# Pi_Wedge.net
KiCad netlist of a schematic drawn in EAGLE
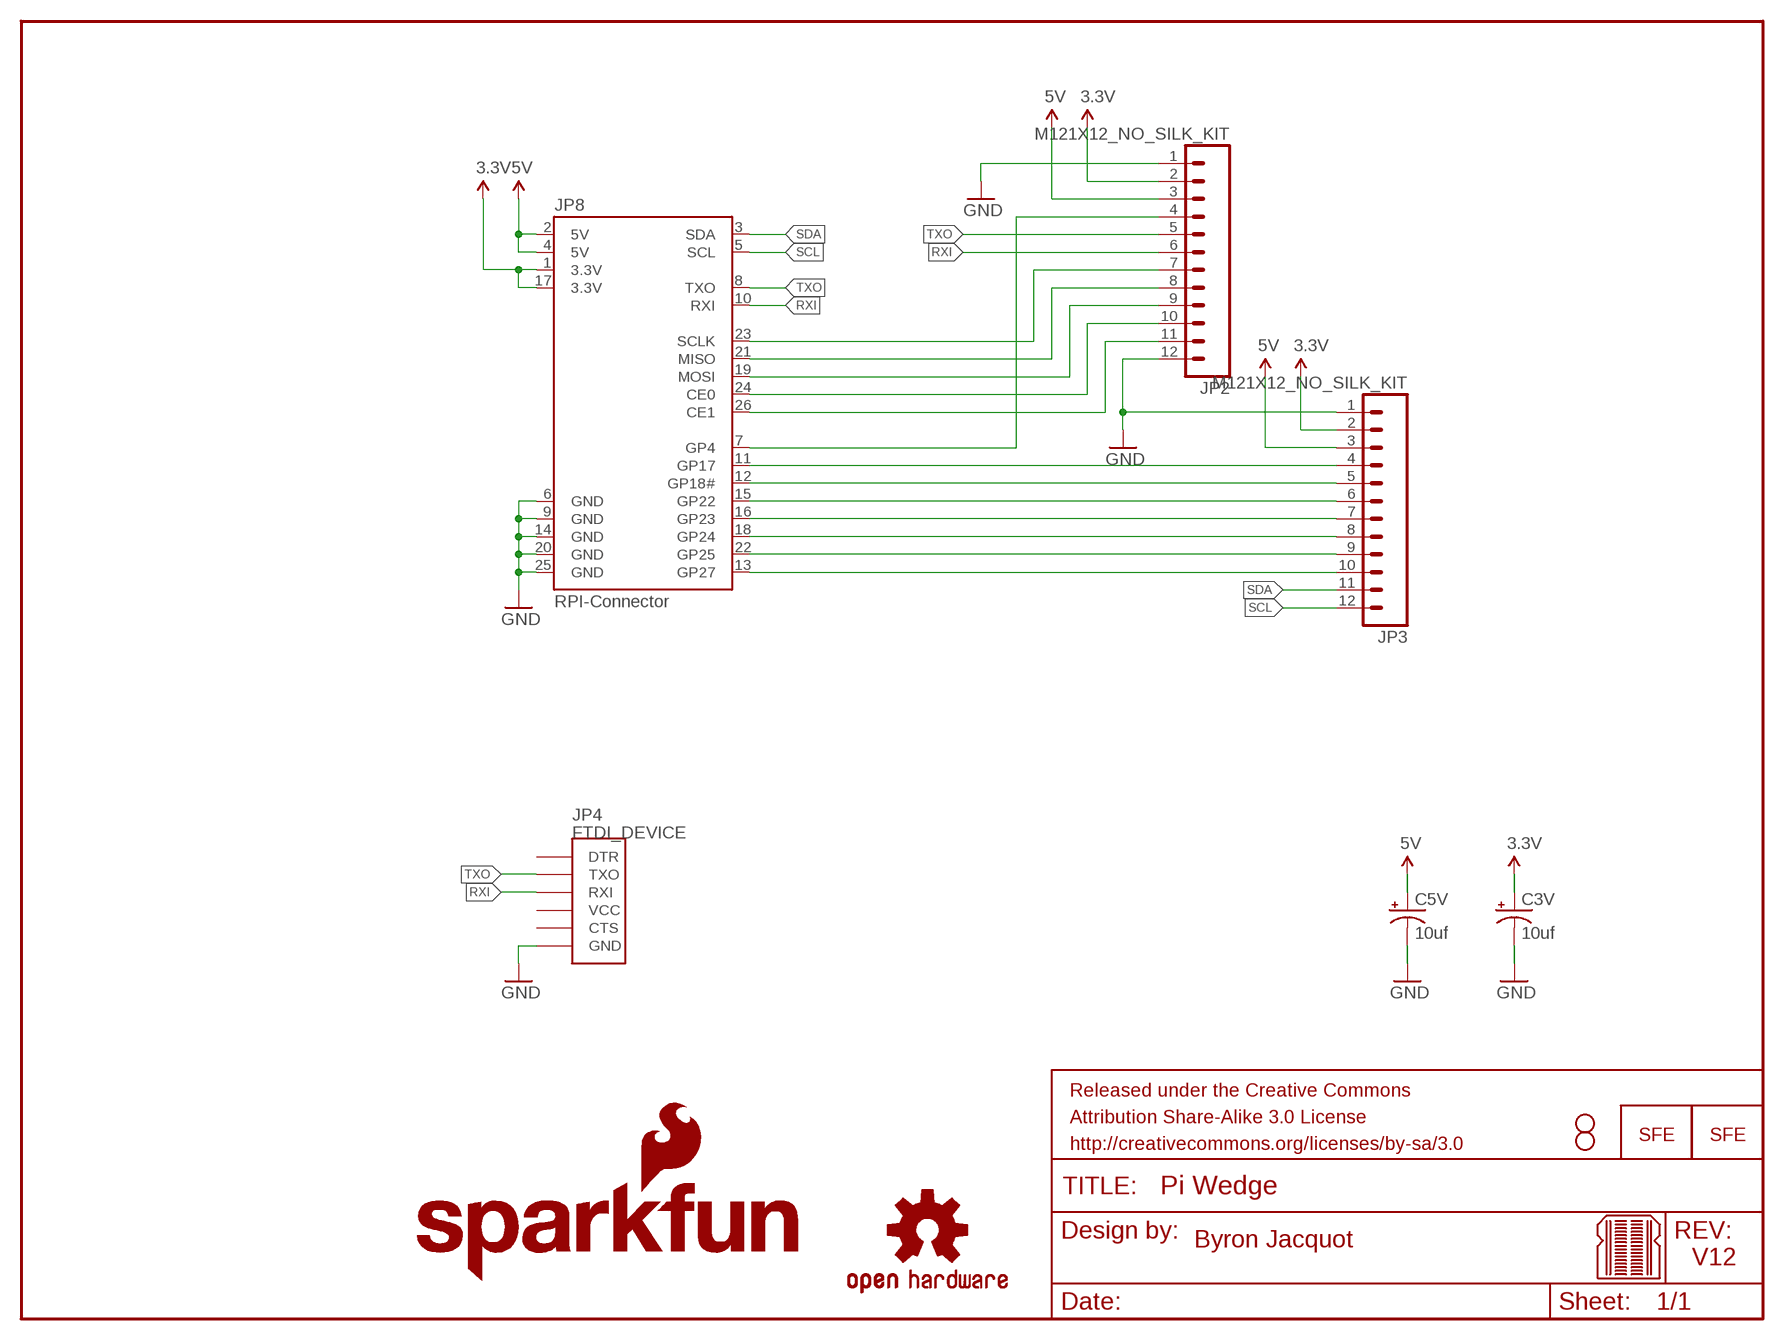
[diagram p0: schematic, sheet 1]

(export (version "E")
  (design (tool "Eeschema 10.0.6"))
  (components
    (comp (ref "C3V")
      (value "10uf")
      (footprint "eagle-import:CPOL-RADIAL-10UF-25V-KIT")
      (libsource (lib "eagle-import") (part "10UF-25V-20%(PTH)KIT"))
    )
    (comp (ref "C5V")
      (value "10uf")
      (footprint "eagle-import:CPOL-RADIAL-10UF-25V-KIT")
      (libsource (lib "eagle-import") (part "10UF-25V-20%(PTH)KIT"))
    )
    (comp (ref "FRAME2")
      (value "FRAME-LETTER")
      (footprint "eagle-import:CREATIVE_COMMONS")
      (libsource (lib "eagle-import") (part "FRAME-LETTER"))
    )
    (comp (ref "JP1")
      (value "LOGO-SFESK")
      (footprint "eagle-import:SFE-LOGO-FLAME")
      (libsource (lib "eagle-import") (part "LOGO-SFESK"))
    )
    (comp (ref "JP2")
      (value "M121X12_NO_SILK_KIT")
      (footprint "eagle-import:1X12_NO_SILK_KIT")
      (libsource (lib "eagle-import") (part "M121X12_NO_SILK_KIT"))
    )
    (comp (ref "JP3")
      (value "M121X12_NO_SILK_KIT")
      (footprint "eagle-import:1X12_NO_SILK_KIT")
      (libsource (lib "eagle-import") (part "M121X12_NO_SILK_KIT"))
    )
    (comp (ref "JP4")
      (value "FTDI_DEVICE")
      (footprint "eagle-import:FTDI_DEVICE_SIDE")
      (libsource (lib "eagle-import") (part "FTDI_DEVICE"))
    )
    (comp (ref "JP5")
      (value "LOGO-SFESK")
      (footprint "eagle-import:SFE-LOGO-FLAME")
      (libsource (lib "eagle-import") (part "LOGO-SFESK"))
    )
    (comp (ref "JP8")
      (value "RPI-Connector")
      (footprint "eagle-import:2X13-SHROUDED")
      (libsource (lib "eagle-import") (part "RASPBERRYPI-GPIOPTH"))
    )
    (comp (ref "LOGO1")
      (value "SFE_LOGO_NAME_FLAME.2_INCH")
      (footprint "eagle-import:SFE_LOGO_NAME_FLAME_.2")
      (libsource (lib "eagle-import") (part "SFE_LOGO_NAME_FLAME.2_INCH"))
    )
    (comp (ref "STANDOFF1")
      (value "STAND-OFF")
      (footprint "eagle-import:STAND-OFF")
      (libsource (lib "eagle-import") (part "STAND-OFF"))
    )
    (comp (ref "STANDOFF2")
      (value "STAND-OFF")
      (footprint "eagle-import:STAND-OFF")
      (libsource (lib "eagle-import") (part "STAND-OFF"))
    )
    (comp (ref "U$1")
      (value "OSHW-LOGOS")
      (footprint "eagle-import:OSHW-LOGO-S")
      (libsource (lib "eagle-import") (part "OSHW-LOGOS"))
    )
    (comp (ref "U$2")
      (value "BREADBOARD_PATTERN")
      (footprint "eagle-import:BREADBOARD_SPACING")
      (libsource (lib "eagle-import") (part "BREADBOARD_PATTERN"))
    )
  )
  (nets
    (net (code "1") (name "3.3V") (class "Default")
      (node (ref "C3V") (pin "1") (pinfunction "+_1") (pintype "passive"))
      (node (ref "JP2") (pin "2") (pinfunction "2_2") (pintype "passive"))
      (node (ref "JP3") (pin "2") (pinfunction "2_2") (pintype "passive"))
      (node (ref "JP8") (pin "1") (pinfunction "3.3V_1") (pintype "power_in"))
      (node (ref "JP8") (pin "17") (pinfunction "3.3V_17") (pintype "power_in"))
    )
    (net (code "2") (name "5V") (class "Default")
      (node (ref "C5V") (pin "1") (pinfunction "+_1") (pintype "passive"))
      (node (ref "JP2") (pin "3") (pinfunction "3_3") (pintype "passive"))
      (node (ref "JP3") (pin "3") (pinfunction "3_3") (pintype "passive"))
      (node (ref "JP8") (pin "2") (pinfunction "5V_2") (pintype "power_in"))
      (node (ref "JP8") (pin "4") (pinfunction "5V_4") (pintype "power_in"))
    )
    (net (code "3") (name "GND") (class "Default")
      (node (ref "C3V") (pin "2") (pinfunction "-_2") (pintype "passive"))
      (node (ref "C5V") (pin "2") (pinfunction "-_2") (pintype "passive"))
      (node (ref "JP2") (pin "1") (pinfunction "1_1") (pintype "passive"))
      (node (ref "JP2") (pin "12") (pinfunction "12_12") (pintype "passive"))
      (node (ref "JP3") (pin "1") (pinfunction "1_1") (pintype "passive"))
      (node (ref "JP4") (pin "P$6") (pinfunction "GND_P$6") (pintype "bidirectional"))
      (node (ref "JP8") (pin "14") (pinfunction "GND_14") (pintype "power_in"))
      (node (ref "JP8") (pin "20") (pinfunction "GND_20") (pintype "power_in"))
      (node (ref "JP8") (pin "25") (pinfunction "GND_25") (pintype "power_in"))
      (node (ref "JP8") (pin "6") (pinfunction "GND_6") (pintype "power_in"))
      (node (ref "JP8") (pin "9") (pinfunction "GND_9") (pintype "power_in"))
    )
    (net (code "4") (name "Net-(JP8-CE0)") (class "Default")
      (node (ref "JP2") (pin "10") (pinfunction "10_10") (pintype "passive"))
      (node (ref "JP8") (pin "24") (pinfunction "CE0_24") (pintype "output"))
    )
    (net (code "5") (name "Net-(JP8-CE1)") (class "Default")
      (node (ref "JP2") (pin "11") (pinfunction "11_11") (pintype "passive"))
      (node (ref "JP8") (pin "26") (pinfunction "CE1_26") (pintype "output"))
    )
    (net (code "6") (name "Net-(JP8-GP4)") (class "Default")
      (node (ref "JP2") (pin "4") (pinfunction "4_4") (pintype "passive"))
      (node (ref "JP8") (pin "7") (pinfunction "GP4_7") (pintype "bidirectional"))
    )
    (net (code "7") (name "Net-(JP8-GP17)") (class "Default")
      (node (ref "JP3") (pin "4") (pinfunction "4_4") (pintype "passive"))
      (node (ref "JP8") (pin "11") (pinfunction "GP17_11") (pintype "bidirectional"))
    )
    (net (code "8") (name "Net-(JP8-GP18#)") (class "Default")
      (node (ref "JP3") (pin "5") (pinfunction "5_5") (pintype "passive"))
      (node (ref "JP8") (pin "12") (pinfunction "GP18#_12") (pintype "bidirectional"))
    )
    (net (code "9") (name "Net-(JP8-GP22)") (class "Default")
      (node (ref "JP3") (pin "6") (pinfunction "6_6") (pintype "passive"))
      (node (ref "JP8") (pin "15") (pinfunction "GP22_15") (pintype "bidirectional"))
    )
    (net (code "10") (name "Net-(JP8-GP23)") (class "Default")
      (node (ref "JP3") (pin "7") (pinfunction "7_7") (pintype "passive"))
      (node (ref "JP8") (pin "16") (pinfunction "GP23_16") (pintype "bidirectional"))
    )
    (net (code "11") (name "Net-(JP8-GP24)") (class "Default")
      (node (ref "JP3") (pin "8") (pinfunction "8_8") (pintype "passive"))
      (node (ref "JP8") (pin "18") (pinfunction "GP24_18") (pintype "bidirectional"))
    )
    (net (code "12") (name "Net-(JP8-GP25)") (class "Default")
      (node (ref "JP3") (pin "9") (pinfunction "9_9") (pintype "passive"))
      (node (ref "JP8") (pin "22") (pinfunction "GP25_22") (pintype "bidirectional"))
    )
    (net (code "13") (name "Net-(JP8-GP27)") (class "Default")
      (node (ref "JP3") (pin "10") (pinfunction "10_10") (pintype "passive"))
      (node (ref "JP8") (pin "13") (pinfunction "GP27_13") (pintype "bidirectional"))
    )
    (net (code "14") (name "Net-(JP8-MISO)") (class "Default")
      (node (ref "JP2") (pin "8") (pinfunction "8_8") (pintype "passive"))
      (node (ref "JP8") (pin "21") (pinfunction "MISO_21") (pintype "input"))
    )
    (net (code "15") (name "Net-(JP8-MOSI)") (class "Default")
      (node (ref "JP2") (pin "9") (pinfunction "9_9") (pintype "passive"))
      (node (ref "JP8") (pin "19") (pinfunction "MOSI_19") (pintype "output"))
    )
    (net (code "16") (name "Net-(JP8-SCLK)") (class "Default")
      (node (ref "JP2") (pin "7") (pinfunction "7_7") (pintype "passive"))
      (node (ref "JP8") (pin "23") (pinfunction "SCLK_23") (pintype "output"))
    )
    (net (code "17") (name "RXI") (class "Default")
      (node (ref "JP2") (pin "6") (pinfunction "6_6") (pintype "passive"))
      (node (ref "JP4") (pin "P$3") (pinfunction "RXI_P$3") (pintype "bidirectional"))
      (node (ref "JP8") (pin "10") (pinfunction "RXI_10") (pintype "input"))
    )
    (net (code "18") (name "SCL") (class "Default")
      (node (ref "JP3") (pin "12") (pinfunction "12_12") (pintype "passive"))
      (node (ref "JP8") (pin "5") (pinfunction "SCL_5") (pintype "bidirectional"))
    )
    (net (code "19") (name "SDA") (class "Default")
      (node (ref "JP3") (pin "11") (pinfunction "11_11") (pintype "passive"))
      (node (ref "JP8") (pin "3") (pinfunction "SDA_3") (pintype "bidirectional"))
    )
    (net (code "20") (name "TXO") (class "Default")
      (node (ref "JP2") (pin "5") (pinfunction "5_5") (pintype "passive"))
      (node (ref "JP4") (pin "P$2") (pinfunction "TXO_P$2") (pintype "bidirectional"))
      (node (ref "JP8") (pin "8") (pinfunction "TXO_8") (pintype "output"))
    )
    (net (code "21") (name "unconnected-(JP4-CTS-PadP$5)") (class "Default")
      (node (ref "JP4") (pin "P$5") (pinfunction "CTS_P$5") (pintype "bidirectional"))
    )
    (net (code "22") (name "unconnected-(JP4-DTR-PadP$1)") (class "Default")
      (node (ref "JP4") (pin "P$1") (pinfunction "DTR_P$1") (pintype "bidirectional"))
    )
    (net (code "23") (name "unconnected-(JP4-VCC-PadP$4)") (class "Default")
      (node (ref "JP4") (pin "P$4") (pinfunction "VCC_P$4") (pintype "bidirectional"))
    )
  )
)
